# TopDesign.net
KiCad netlist of a schematic drawn in Altium Designer
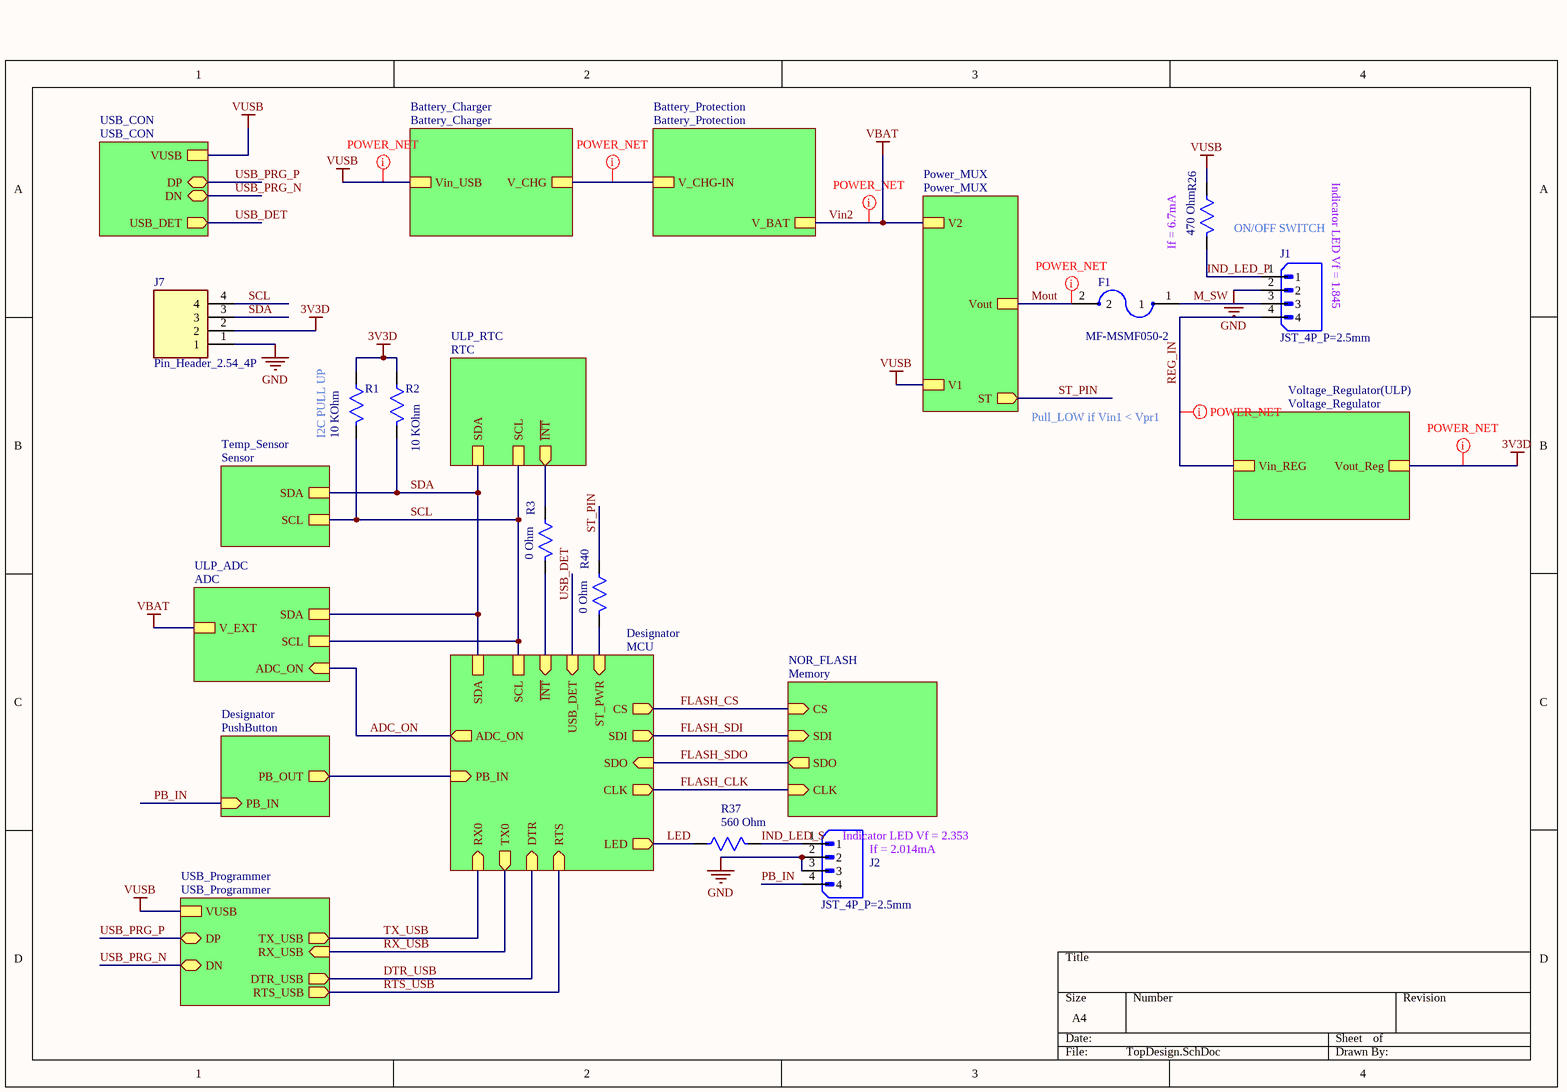
[diagram p0: TopDesign.SchDoc]

(export (version "E")
  (design (tool "Eeschema 10.0.6"))
  (components
    (comp (ref "F1")
      (value "MF-MSMF050-2")
      (footprint "Fuse_SMD_1812_1A")
      (description "Polymeric PTC Resettable Fuse 15V 500 mA Ih Surface Mount 1812 (4532 Metric), Concave")
      (fields (field (name "MF") "Bourns"))
      (libsource (lib "Aptinex_discrete") (part "MF-MSMF050-2"))
    )
    (comp (ref "J1")
      (value "JST_4P_P=2.5mm")
      (footprint "JST_4P_Straight_P=2.5mm")
      (description "Connector Header Through Hole 4 position 0.098 (2.50mm)")
      (fields (field (name "MF") "JST Sales") (field (name "MP") "B4B-XH-A(LF)(SN)"))
      (libsource (lib "Aptinex_connectors") (part "JST_4P_P=2.5mm"))
    )
    (comp (ref "J2")
      (value "JST_4P_P=2.5mm")
      (footprint "JST_4P_Straight_P=2.5mm")
      (description "Connector Header Through Hole 4 position 0.098 (2.50mm)")
      (fields (field (name "MF") "JST Sales") (field (name "MP") "B4B-XH-A(LF)(SN)"))
      (libsource (lib "Aptinex_connectors") (part "JST_4P_P=2.5mm"))
    )
    (comp (ref "J7")
      (value "Pin_Header_2.54_4P")
      (footprint "Pin_Header_2.54_4P")
      (description "Pin_Header_2.54_2P X 4 MF: 22-28-4050")
      (fields
        (field (name "MANUFACTURER_PART_NUMBER") "22-28-4050")
        (field (name "MOUSER PART NUMBER") "538-22-28-4050")
      )
      (libsource (lib "Aptinex_connectors") (part "Pin_Header_2.54_4P"))
    )
    (comp (ref "R1")
      (value "10 KOhm")
      (footprint "Res_0603")
      (description "SMD Resistor")
      (fields (field (name "MP") "RC0805FR-07330RL") (field (name "MF") "Yageo"))
      (libsource (lib "Aptinex_discrete") (part "Res smd"))
    )
    (comp (ref "R2")
      (value "10 KOhm")
      (footprint "Res_0603")
      (description "SMD Resistor")
      (fields (field (name "MP") "RC0805FR-07330RL") (field (name "MF") "Yageo"))
      (libsource (lib "Aptinex_discrete") (part "Res smd"))
    )
    (comp (ref "R3")
      (value "0 Ohm")
      (footprint "RES_0402")
      (description "SMD Resistor")
      (fields (field (name "MP") "RC0805FR-07330RL") (field (name "MF") "Yageo"))
      (libsource (lib "Aptinex_discrete") (part "Res smd"))
    )
    (comp (ref "R26")
      (value "470 Ohm")
      (footprint "Res_0603")
      (description "SMD Resistor")
      (fields (field (name "MP") "RC0805FR-07330RL") (field (name "MF") "Yageo"))
      (libsource (lib "Aptinex_discrete") (part "Res smd"))
    )
    (comp (ref "R37")
      (value "560 Ohm")
      (footprint "Res_0603")
      (description "SMD Resistor")
      (fields (field (name "MP") "RC0805FR-07330RL") (field (name "MF") "Yageo"))
      (libsource (lib "Aptinex_discrete") (part "Res smd"))
    )
    (comp (ref "R40")
      (value "0 Ohm")
      (footprint "RES_0402")
      (description "SMD Resistor")
      (fields (field (name "MP") "RC0805FR-07330RL") (field (name "MF") "Yageo"))
      (libsource (lib "Aptinex_discrete") (part "Res smd"))
    )
  )
  (nets
    (net (code "7") (name "/IND_LED_P") (class "Default")
      (node (ref "J1") (pin "1") (pinfunction "1_1") (pintype "passive"))
      (node (ref "R26") (pin "1") (pinfunction "1_1") (pintype "passive"))
    )
    (net (code "8") (name "/IND_LED_S") (class "Default")
      (node (ref "J2") (pin "1") (pinfunction "1_1") (pintype "passive"))
      (node (ref "R37") (pin "1") (pinfunction "1_1") (pintype "passive"))
    )
    (net (code "9") (name "/LED") (class "Default")
      (node (ref "R37") (pin "2") (pinfunction "2_2") (pintype "passive"))
    )
    (net (code "10") (name "/M_SW") (class "Default")
      (node (ref "F1") (pin "1") (pinfunction "1_1") (pintype "passive"))
      (node (ref "J1") (pin "3") (pinfunction "3_3") (pintype "passive"))
    )
    (net (code "11") (name "/Mout") (class "Default")
      (node (ref "F1") (pin "2") (pinfunction "2_2") (pintype "passive"))
    )
    (net (code "12") (name "/PB_IN") (class "Default")
      (node (ref "J2") (pin "4") (pinfunction "4_4") (pintype "passive"))
    )
    (net (code "14") (name "/REG_IN") (class "Default")
      (node (ref "J1") (pin "4") (pinfunction "4_4") (pintype "passive"))
    )
    (net (code "17") (name "/SCL") (class "Default")
      (node (ref "J7") (pin "4") (pinfunction "4_4") (pintype "passive"))
      (node (ref "R1") (pin "1") (pinfunction "1_1") (pintype "passive"))
    )
    (net (code "18") (name "/SDA") (class "Default")
      (node (ref "J7") (pin "3") (pinfunction "3_3") (pintype "passive"))
      (node (ref "R2") (pin "1") (pinfunction "1_1") (pintype "passive"))
    )
    (net (code "19") (name "/ST_PIN") (class "Default")
      (node (ref "R40") (pin "2") (pinfunction "2_2") (pintype "passive"))
    )
    (net (code "20") (name "/ST_PWR") (class "Default")
      (node (ref "R40") (pin "1") (pinfunction "1_1") (pintype "passive"))
    )
    (net (code "26") (name "/~{INT}") (class "Default")
      (node (ref "R3") (pin "2") (pinfunction "2_2") (pintype "passive"))
    )
    (net (code "27") (name "/~{INT}_1") (class "Default")
      (node (ref "R3") (pin "1") (pinfunction "1_1") (pintype "passive"))
    )
    (net (code "28") (name "3V3D") (class "Default")
      (node (ref "J7") (pin "2") (pinfunction "2_2") (pintype "passive"))
      (node (ref "R1") (pin "2") (pinfunction "2_2") (pintype "passive"))
      (node (ref "R2") (pin "2") (pinfunction "2_2") (pintype "passive"))
    )
    (net (code "29") (name "GND") (class "Default")
      (node (ref "J1") (pin "2") (pinfunction "2_2") (pintype "passive"))
      (node (ref "J2") (pin "2") (pinfunction "2_2") (pintype "passive"))
      (node (ref "J2") (pin "3") (pinfunction "3_3") (pintype "passive"))
      (node (ref "J7") (pin "1") (pinfunction "1_1") (pintype "passive"))
    )
    (net (code "31") (name "VUSB") (class "Default")
      (node (ref "R26") (pin "2") (pinfunction "2_2") (pintype "passive"))
    )
  )
)
